# rotary-control.net
KiCad netlist of a schematic drawn in EAGLE
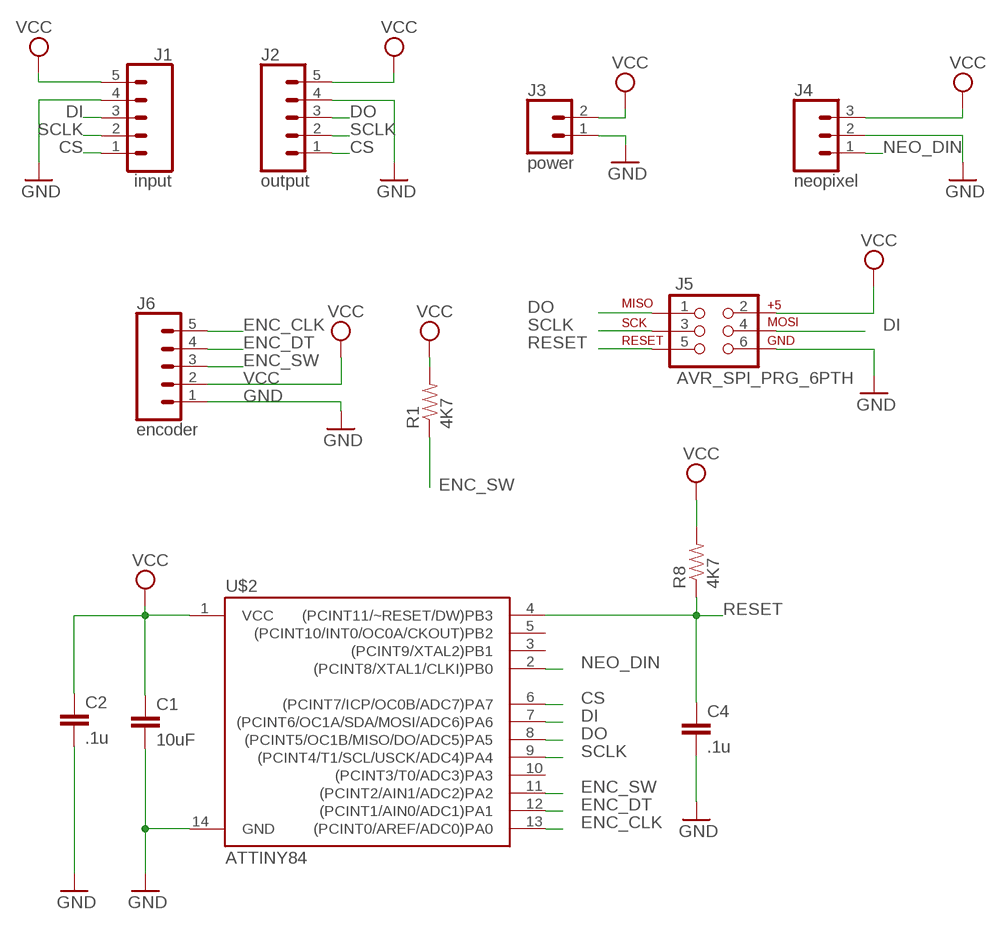
[diagram p0: schematic, sheet 1]

(export (version "E")
  (design (tool "Eeschema 10.0.6"))
  (components
    (comp (ref "C1")
      (value "10uF")
      (footprint "eagle-import:1206")
      (libsource (lib "eagle-import") (part "10UF-1206-6.3V-20%"))
    )
    (comp (ref "C2")
      (value ".1u")
      (footprint "eagle-import:0805")
      (libsource (lib "eagle-import") (part "CAP0805"))
    )
    (comp (ref "C4")
      (value ".1u")
      (footprint "eagle-import:0805")
      (libsource (lib "eagle-import") (part "CAP0805"))
    )
    (comp (ref "J1")
      (value "input")
      (footprint "eagle-import:1X05")
      (libsource (lib "eagle-import") (part "CONN_05"))
    )
    (comp (ref "J2")
      (value "output")
      (footprint "eagle-import:1X05")
      (libsource (lib "eagle-import") (part "CONN_05"))
    )
    (comp (ref "J3")
      (value "power")
      (footprint "eagle-import:1X02")
      (libsource (lib "eagle-import") (part "CONN_02"))
    )
    (comp (ref "J4")
      (value "neopixel")
      (footprint "eagle-import:1X03")
      (libsource (lib "eagle-import") (part "CONN_03"))
    )
    (comp (ref "J5")
      (value "AVR_SPI_PRG_6PTH")
      (footprint "eagle-import:2X3")
      (libsource (lib "eagle-import") (part "AVR_SPI_PRG_6PTH"))
    )
    (comp (ref "J6")
      (value "encoder")
      (footprint "eagle-import:1X05")
      (libsource (lib "eagle-import") (part "CONN_05"))
    )
    (comp (ref "R1")
      (value "4K7")
      (footprint "eagle-import:0805")
      (libsource (lib "eagle-import") (part "RESISTOR"))
    )
    (comp (ref "R8")
      (value "4K7")
      (footprint "eagle-import:0805")
      (libsource (lib "eagle-import") (part "RESISTOR"))
    )
    (comp (ref "U$2")
      (value "ATTINY84")
      (footprint "eagle-import:SO14")
      (libsource (lib "eagle-import") (part "ATTINY84"))
    )
  )
  (nets
    (net (code "1") (name "/CS") (class "Default")
      (node (ref "J1") (pin "1") (pinfunction "1_1") (pintype "passive"))
      (node (ref "J2") (pin "1") (pinfunction "1_1") (pintype "passive"))
      (node (ref "U$2") (pin "6") (pinfunction "(PCINT7/ICP/OC0B/ADC7)PA7_6") (pintype "bidirectional"))
    )
    (net (code "2") (name "/DI") (class "Default")
      (node (ref "J1") (pin "3") (pinfunction "3_3") (pintype "passive"))
      (node (ref "J5") (pin "4") (pinfunction "4_4") (pintype "passive"))
      (node (ref "U$2") (pin "7") (pinfunction "(PCINT6/OC1A/SDA/MOSI/ADC6)PA6_7") (pintype "bidirectional"))
    )
    (net (code "3") (name "/DO") (class "Default")
      (node (ref "J2") (pin "3") (pinfunction "3_3") (pintype "passive"))
      (node (ref "J5") (pin "1") (pinfunction "1_1") (pintype "passive"))
      (node (ref "U$2") (pin "8") (pinfunction "(PCINT5/OC1B/MISO/DO/ADC5)PA5_8") (pintype "bidirectional"))
    )
    (net (code "4") (name "/ENC_CLK") (class "Default")
      (node (ref "J6") (pin "5") (pinfunction "5_5") (pintype "passive"))
      (node (ref "U$2") (pin "13") (pinfunction "(PCINT0/AREF/ADC0)PA0_13") (pintype "bidirectional"))
    )
    (net (code "5") (name "/ENC_DT") (class "Default")
      (node (ref "J6") (pin "4") (pinfunction "4_4") (pintype "passive"))
      (node (ref "U$2") (pin "12") (pinfunction "(PCINT1/AIN0/ADC1)PA1_12") (pintype "bidirectional"))
    )
    (net (code "6") (name "/ENC_SW") (class "Default")
      (node (ref "J6") (pin "3") (pinfunction "3_3") (pintype "passive"))
      (node (ref "R1") (pin "1") (pinfunction "1_1") (pintype "passive"))
      (node (ref "U$2") (pin "11") (pinfunction "(PCINT2/AIN1/ADC2)PA2_11") (pintype "bidirectional"))
    )
    (net (code "7") (name "/NEO_DIN") (class "Default")
      (node (ref "J4") (pin "1") (pinfunction "1_1") (pintype "passive"))
      (node (ref "U$2") (pin "2") (pinfunction "(PCINT8/XTAL1/CLKI)PB0_2") (pintype "bidirectional"))
    )
    (net (code "8") (name "/RESET") (class "Default")
      (node (ref "C4") (pin "1") (pinfunction "1_1") (pintype "passive"))
      (node (ref "J5") (pin "5") (pinfunction "5_5") (pintype "passive"))
      (node (ref "R8") (pin "1") (pinfunction "1_1") (pintype "passive"))
      (node (ref "U$2") (pin "4") (pinfunction "(PCINT11/~{RESET/DW})PB3_4") (pintype "bidirectional"))
    )
    (net (code "9") (name "/SCLK") (class "Default")
      (node (ref "J1") (pin "2") (pinfunction "2_2") (pintype "passive"))
      (node (ref "J2") (pin "2") (pinfunction "2_2") (pintype "passive"))
      (node (ref "J5") (pin "3") (pinfunction "3_3") (pintype "passive"))
      (node (ref "U$2") (pin "9") (pinfunction "(PCINT4/T1/SCL/USCK/ADC4)PA4_9") (pintype "bidirectional"))
    )
    (net (code "10") (name "GND") (class "Default")
      (node (ref "C1") (pin "2") (pinfunction "2_2") (pintype "passive"))
      (node (ref "C2") (pin "2") (pinfunction "2_2") (pintype "passive"))
      (node (ref "C4") (pin "2") (pinfunction "2_2") (pintype "passive"))
      (node (ref "J1") (pin "4") (pinfunction "4_4") (pintype "passive"))
      (node (ref "J2") (pin "4") (pinfunction "4_4") (pintype "passive"))
      (node (ref "J3") (pin "1") (pinfunction "1_1") (pintype "passive"))
      (node (ref "J4") (pin "2") (pinfunction "2_2") (pintype "passive"))
      (node (ref "J5") (pin "6") (pinfunction "6_6") (pintype "passive"))
      (node (ref "J6") (pin "1") (pinfunction "1_1") (pintype "passive"))
      (node (ref "U$2") (pin "14") (pinfunction "GND_14") (pintype "bidirectional"))
    )
    (net (code "11") (name "VCC") (class "Default")
      (node (ref "C1") (pin "1") (pinfunction "1_1") (pintype "passive"))
      (node (ref "C2") (pin "1") (pinfunction "1_1") (pintype "passive"))
      (node (ref "J1") (pin "5") (pinfunction "5_5") (pintype "passive"))
      (node (ref "J2") (pin "5") (pinfunction "5_5") (pintype "passive"))
      (node (ref "J3") (pin "2") (pinfunction "2_2") (pintype "passive"))
      (node (ref "J4") (pin "3") (pinfunction "3_3") (pintype "passive"))
      (node (ref "J5") (pin "2") (pinfunction "2_2") (pintype "passive"))
      (node (ref "J6") (pin "2") (pinfunction "2_2") (pintype "passive"))
      (node (ref "R1") (pin "2") (pinfunction "2_2") (pintype "passive"))
      (node (ref "R8") (pin "2") (pinfunction "2_2") (pintype "passive"))
      (node (ref "U$2") (pin "1") (pinfunction "VCC_1") (pintype "bidirectional"))
    )
    (net (code "12") (name "unconnected-(U$2-(PCINT3{slash}T0{slash}ADC3)PA3-Pad10)") (class "Default")
      (node (ref "U$2") (pin "10") (pinfunction "(PCINT3/T0/ADC3)PA3_10") (pintype "bidirectional"))
    )
    (net (code "13") (name "unconnected-(U$2-(PCINT9{slash}XTAL2)PB1-Pad3)") (class "Default")
      (node (ref "U$2") (pin "3") (pinfunction "(PCINT9/XTAL2)PB1_3") (pintype "bidirectional"))
    )
    (net (code "14") (name "unconnected-(U$2-(PCINT10{slash}INT0{slash}OC0A{slash}CKOUT)PB2-Pad5)") (class "Default")
      (node (ref "U$2") (pin "5") (pinfunction "(PCINT10/INT0/OC0A/CKOUT)PB2_5") (pintype "bidirectional"))
    )
  )
)
